# LowTemp_board_2.net
KiCad netlist of a schematic drawn in EAGLE
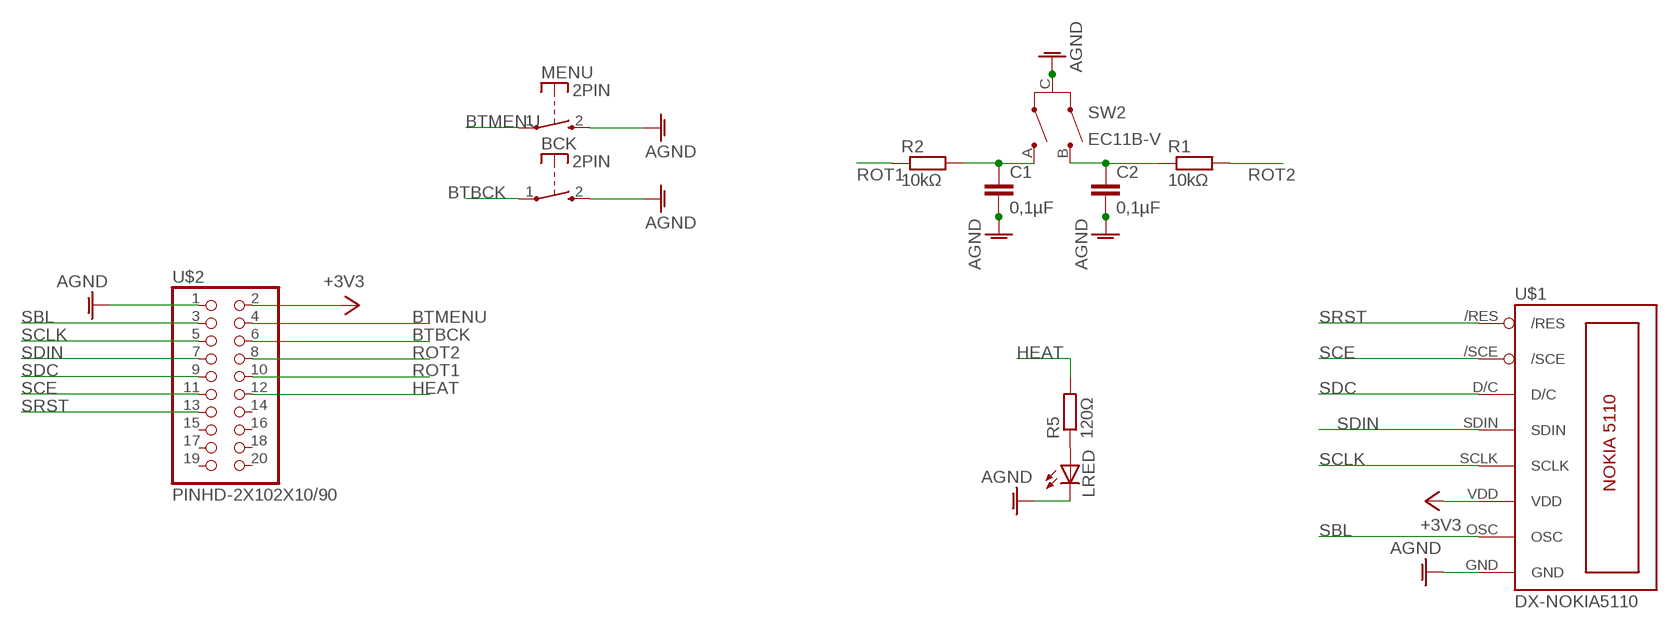
[diagram p0: schematic, sheet 1]

(export (version "E")
  (design (tool "Eeschema 10.0.6"))
  (components
    (comp (ref "BCK")
      (value "2PIN")
      (footprint "eagle-import:2PIN")
      (libsource (lib "eagle-import") (part "2PIN"))
    )
    (comp (ref "C1")
      (value "0,1µF")
      (footprint "eagle-import:C050-025X075")
      (libsource (lib "eagle-import") (part "C-EU050-025X075"))
    )
    (comp (ref "C2")
      (value "0,1µF")
      (footprint "eagle-import:C050-025X075")
      (libsource (lib "eagle-import") (part "C-EU050-025X075"))
    )
    (comp (ref "LRED")
      (value "LED5MM")
      (footprint "eagle-import:LED5MM")
      (libsource (lib "eagle-import") (part "LED5MM"))
    )
    (comp (ref "MENU")
      (value "2PIN")
      (footprint "eagle-import:2PIN")
      (libsource (lib "eagle-import") (part "2PIN"))
    )
    (comp (ref "R1")
      (value "10kΩ")
      (footprint "eagle-import:0207_7")
      (libsource (lib "eagle-import") (part "R-EU_0207/7"))
    )
    (comp (ref "R2")
      (value "10kΩ")
      (footprint "eagle-import:0207_7")
      (libsource (lib "eagle-import") (part "R-EU_0207/7"))
    )
    (comp (ref "R5")
      (value "120Ω")
      (footprint "eagle-import:0207_7")
      (libsource (lib "eagle-import") (part "R-EU_0207/7"))
    )
    (comp (ref "SW2")
      (value "EC11B-V")
      (footprint "eagle-import:EC11B-V")
      (libsource (lib "eagle-import") (part "EC11B-V"))
    )
    (comp (ref "U$1")
      (value "DX-NOKIA5110")
      (footprint "eagle-import:DX-NOKIA5110")
      (libsource (lib "eagle-import") (part "DX-NOKIA5110"))
    )
    (comp (ref "U$2")
      (value "PINHD-2X102X10/90")
      (footprint "eagle-import:2X10_90")
      (libsource (lib "eagle-import") (part "PINHD-2X102X10/90"))
    )
  )
  (nets
    (net (code "1") (name "+3V3") (class "Default")
      (node (ref "U$1") (pin "VDD") (pinfunction "VDD_VDD") (pintype "power_in"))
      (node (ref "U$2") (pin "2") (pinfunction "2_2") (pintype "passive"))
    )
    (net (code "2") (name "/BTBCK") (class "Default")
      (node (ref "BCK") (pin "1") (pinfunction "P_1") (pintype "passive"))
      (node (ref "U$2") (pin "6") (pinfunction "6_6") (pintype "passive"))
    )
    (net (code "3") (name "/BTMENU") (class "Default")
      (node (ref "MENU") (pin "1") (pinfunction "P_1") (pintype "passive"))
      (node (ref "U$2") (pin "4") (pinfunction "4_4") (pintype "passive"))
    )
    (net (code "4") (name "/HEAT") (class "Default")
      (node (ref "R5") (pin "2") (pinfunction "2_2") (pintype "passive"))
      (node (ref "U$2") (pin "12") (pinfunction "12_12") (pintype "passive"))
    )
    (net (code "5") (name "/ROT1") (class "Default")
      (node (ref "R2") (pin "1") (pinfunction "1_1") (pintype "passive"))
      (node (ref "U$2") (pin "10") (pinfunction "10_10") (pintype "passive"))
    )
    (net (code "6") (name "/ROT2") (class "Default")
      (node (ref "R1") (pin "2") (pinfunction "2_2") (pintype "passive"))
      (node (ref "U$2") (pin "8") (pinfunction "8_8") (pintype "passive"))
    )
    (net (code "7") (name "/SBL") (class "Default")
      (node (ref "U$1") (pin "OSC") (pinfunction "OSC_OSC") (pintype "input"))
      (node (ref "U$2") (pin "3") (pinfunction "3_3") (pintype "passive"))
    )
    (net (code "8") (name "/SCE") (class "Default")
      (node (ref "U$1") (pin "/SCE") (pinfunction "/SCE_/SCE") (pintype "input"))
      (node (ref "U$2") (pin "11") (pinfunction "11_11") (pintype "passive"))
    )
    (net (code "9") (name "/SCLK") (class "Default")
      (node (ref "U$1") (pin "SCLK") (pinfunction "SCLK_SCLK") (pintype "input"))
      (node (ref "U$2") (pin "5") (pinfunction "5_5") (pintype "passive"))
    )
    (net (code "10") (name "/SDC") (class "Default")
      (node (ref "U$1") (pin "D/C") (pinfunction "D/C_D/C") (pintype "input"))
      (node (ref "U$2") (pin "9") (pinfunction "9_9") (pintype "passive"))
    )
    (net (code "11") (name "/SDIN") (class "Default")
      (node (ref "U$1") (pin "SDIN") (pinfunction "SDIN_SDIN") (pintype "input"))
      (node (ref "U$2") (pin "7") (pinfunction "7_7") (pintype "passive"))
    )
    (net (code "12") (name "/SRST") (class "Default")
      (node (ref "U$1") (pin "/RES") (pinfunction "/RES_/RES") (pintype "input"))
      (node (ref "U$2") (pin "13") (pinfunction "13_13") (pintype "passive"))
    )
    (net (code "13") (name "AGND") (class "Default")
      (node (ref "BCK") (pin "2") (pinfunction "S_2") (pintype "passive"))
      (node (ref "C1") (pin "2") (pinfunction "2_2") (pintype "passive"))
      (node (ref "C2") (pin "2") (pinfunction "2_2") (pintype "passive"))
      (node (ref "LRED") (pin "K") (pinfunction "C_K") (pintype "passive"))
      (node (ref "MENU") (pin "2") (pinfunction "S_2") (pintype "passive"))
      (node (ref "SW2") (pin "C") (pinfunction "C_C") (pintype "passive"))
      (node (ref "U$1") (pin "GND") (pinfunction "GND_GND") (pintype "power_in"))
      (node (ref "U$2") (pin "1") (pinfunction "1_1") (pintype "passive"))
    )
    (net (code "14") (name "Net-(C1-Pad1)") (class "Default")
      (node (ref "C1") (pin "1") (pinfunction "1_1") (pintype "passive"))
      (node (ref "R2") (pin "2") (pinfunction "2_2") (pintype "passive"))
      (node (ref "SW2") (pin "A") (pinfunction "A_A") (pintype "passive"))
    )
    (net (code "15") (name "Net-(C2-Pad1)") (class "Default")
      (node (ref "C2") (pin "1") (pinfunction "1_1") (pintype "passive"))
      (node (ref "R1") (pin "1") (pinfunction "1_1") (pintype "passive"))
      (node (ref "SW2") (pin "B") (pinfunction "B_B") (pintype "passive"))
    )
    (net (code "16") (name "Net-(LRED-PadA)") (class "Default")
      (node (ref "LRED") (pin "A") (pinfunction "A_A") (pintype "passive"))
      (node (ref "R5") (pin "1") (pinfunction "1_1") (pintype "passive"))
    )
    (net (code "17") (name "unconnected-(U$2-Pad14)") (class "Default")
      (node (ref "U$2") (pin "14") (pinfunction "14_14") (pintype "passive"))
    )
    (net (code "18") (name "unconnected-(U$2-Pad15)") (class "Default")
      (node (ref "U$2") (pin "15") (pinfunction "15_15") (pintype "passive"))
    )
    (net (code "19") (name "unconnected-(U$2-Pad16)") (class "Default")
      (node (ref "U$2") (pin "16") (pinfunction "16_16") (pintype "passive"))
    )
    (net (code "20") (name "unconnected-(U$2-Pad17)") (class "Default")
      (node (ref "U$2") (pin "17") (pinfunction "17_17") (pintype "passive"))
    )
    (net (code "21") (name "unconnected-(U$2-Pad18)") (class "Default")
      (node (ref "U$2") (pin "18") (pinfunction "18_18") (pintype "passive"))
    )
    (net (code "22") (name "unconnected-(U$2-Pad19)") (class "Default")
      (node (ref "U$2") (pin "19") (pinfunction "19_19") (pintype "passive"))
    )
    (net (code "23") (name "unconnected-(U$2-Pad20)") (class "Default")
      (node (ref "U$2") (pin "20") (pinfunction "20_20") (pintype "passive"))
    )
  )
)
